# hub.net
KiCad netlist of a schematic drawn in EAGLE
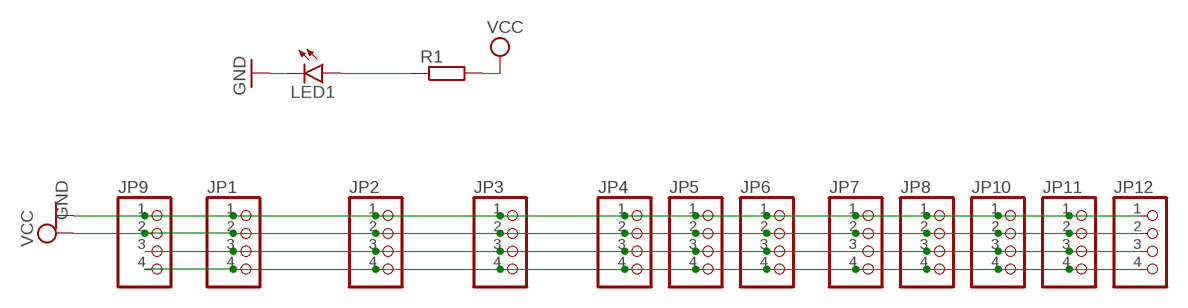
[diagram p0: schematic, sheet 1]

(export (version "E")
  (design (tool "Eeschema 10.0.6"))
  (components
    (comp (ref "JP1")
      (value "PINHD-1X04_2.54-SMD")
      (footprint "eagle-import:1X04SMD")
      (libsource (lib "eagle-import") (part "PINHD-1X04_2.54-SMD"))
    )
    (comp (ref "JP2")
      (value "PINHD-1X04_2.54-SMD")
      (footprint "eagle-import:1X04SMD")
      (libsource (lib "eagle-import") (part "PINHD-1X04_2.54-SMD"))
    )
    (comp (ref "JP3")
      (value "PINHD-1X04_2.54-SMD")
      (footprint "eagle-import:1X04SMD")
      (libsource (lib "eagle-import") (part "PINHD-1X04_2.54-SMD"))
    )
    (comp (ref "JP4")
      (value "PINHD-1X04_2.54-SMD")
      (footprint "eagle-import:1X04SMD")
      (libsource (lib "eagle-import") (part "PINHD-1X04_2.54-SMD"))
    )
    (comp (ref "JP5")
      (value "PINHD-1X04_2.54-SMD")
      (footprint "eagle-import:1X04SMD")
      (libsource (lib "eagle-import") (part "PINHD-1X04_2.54-SMD"))
    )
    (comp (ref "JP6")
      (value "PINHD-1X04_2.54-SMD")
      (footprint "eagle-import:1X04SMD")
      (libsource (lib "eagle-import") (part "PINHD-1X04_2.54-SMD"))
    )
    (comp (ref "JP7")
      (value "PINHD-1X04_2.54-SMD")
      (footprint "eagle-import:1X04SMD")
      (libsource (lib "eagle-import") (part "PINHD-1X04_2.54-SMD"))
    )
    (comp (ref "JP8")
      (value "PINHD-1X04_2.54-SMD")
      (footprint "eagle-import:1X04SMD")
      (libsource (lib "eagle-import") (part "PINHD-1X04_2.54-SMD"))
    )
    (comp (ref "JP9")
      (value "PINHD-1X04_2.54-SMD")
      (footprint "eagle-import:1X04SMD")
      (libsource (lib "eagle-import") (part "PINHD-1X04_2.54-SMD"))
    )
    (comp (ref "JP10")
      (value "PINHD-1X04_2.54-SMD")
      (footprint "eagle-import:1X04SMD")
      (libsource (lib "eagle-import") (part "PINHD-1X04_2.54-SMD"))
    )
    (comp (ref "JP11")
      (value "PINHD-1X04_2.54-SMD")
      (footprint "eagle-import:1X04SMD")
      (libsource (lib "eagle-import") (part "PINHD-1X04_2.54-SMD"))
    )
    (comp (ref "JP12")
      (value "PINHD-1X04_2.54-SMD")
      (footprint "eagle-import:1X04SMD")
      (libsource (lib "eagle-import") (part "PINHD-1X04_2.54-SMD"))
    )
    (comp (ref "LED1")
      (value "LEDCHIPLED_1206")
      (footprint "eagle-import:CHIPLED_1206")
      (libsource (lib "eagle-import") (part "LEDCHIPLED_1206"))
    )
    (comp (ref "R1")
      (value "R-EU_R1206")
      (footprint "eagle-import:R1206")
      (libsource (lib "eagle-import") (part "R-EU_R1206"))
    )
  )
  (nets
    (net (code "1") (name "GND") (class "Default")
      (node (ref "JP1") (pin "1") (pinfunction "1_1") (pintype "passive"))
      (node (ref "JP10") (pin "1") (pinfunction "1_1") (pintype "passive"))
      (node (ref "JP11") (pin "1") (pinfunction "1_1") (pintype "passive"))
      (node (ref "JP12") (pin "1") (pinfunction "1_1") (pintype "passive"))
      (node (ref "JP2") (pin "1") (pinfunction "1_1") (pintype "passive"))
      (node (ref "JP3") (pin "1") (pinfunction "1_1") (pintype "passive"))
      (node (ref "JP4") (pin "1") (pinfunction "1_1") (pintype "passive"))
      (node (ref "JP5") (pin "1") (pinfunction "1_1") (pintype "passive"))
      (node (ref "JP6") (pin "1") (pinfunction "1_1") (pintype "passive"))
      (node (ref "JP7") (pin "1") (pinfunction "1_1") (pintype "passive"))
      (node (ref "JP8") (pin "1") (pinfunction "1_1") (pintype "passive"))
      (node (ref "JP9") (pin "1") (pinfunction "1_1") (pintype "passive"))
      (node (ref "LED1") (pin "C") (pinfunction "C_C") (pintype "passive"))
    )
    (net (code "2") (name "Net-(JP1-Pad3)") (class "Default")
      (node (ref "JP1") (pin "3") (pinfunction "3_3") (pintype "passive"))
      (node (ref "JP10") (pin "3") (pinfunction "3_3") (pintype "passive"))
      (node (ref "JP11") (pin "3") (pinfunction "3_3") (pintype "passive"))
      (node (ref "JP12") (pin "3") (pinfunction "3_3") (pintype "passive"))
      (node (ref "JP2") (pin "3") (pinfunction "3_3") (pintype "passive"))
      (node (ref "JP3") (pin "3") (pinfunction "3_3") (pintype "passive"))
      (node (ref "JP4") (pin "3") (pinfunction "3_3") (pintype "passive"))
      (node (ref "JP5") (pin "3") (pinfunction "3_3") (pintype "passive"))
      (node (ref "JP6") (pin "3") (pinfunction "3_3") (pintype "passive"))
      (node (ref "JP7") (pin "3") (pinfunction "3_3") (pintype "passive"))
      (node (ref "JP8") (pin "3") (pinfunction "3_3") (pintype "passive"))
      (node (ref "JP9") (pin "3") (pinfunction "3_3") (pintype "passive"))
    )
    (net (code "3") (name "Net-(JP1-Pad4)") (class "Default")
      (node (ref "JP1") (pin "4") (pinfunction "4_4") (pintype "passive"))
      (node (ref "JP10") (pin "4") (pinfunction "4_4") (pintype "passive"))
      (node (ref "JP11") (pin "4") (pinfunction "4_4") (pintype "passive"))
      (node (ref "JP12") (pin "4") (pinfunction "4_4") (pintype "passive"))
      (node (ref "JP2") (pin "4") (pinfunction "4_4") (pintype "passive"))
      (node (ref "JP3") (pin "4") (pinfunction "4_4") (pintype "passive"))
      (node (ref "JP4") (pin "4") (pinfunction "4_4") (pintype "passive"))
      (node (ref "JP5") (pin "4") (pinfunction "4_4") (pintype "passive"))
      (node (ref "JP6") (pin "4") (pinfunction "4_4") (pintype "passive"))
      (node (ref "JP7") (pin "4") (pinfunction "4_4") (pintype "passive"))
      (node (ref "JP8") (pin "4") (pinfunction "4_4") (pintype "passive"))
      (node (ref "JP9") (pin "4") (pinfunction "4_4") (pintype "passive"))
    )
    (net (code "4") (name "Net-(LED1-PadA)") (class "Default")
      (node (ref "LED1") (pin "A") (pinfunction "A_A") (pintype "passive"))
      (node (ref "R1") (pin "1") (pinfunction "1_1") (pintype "passive"))
    )
    (net (code "5") (name "VCC") (class "Default")
      (node (ref "JP1") (pin "2") (pinfunction "2_2") (pintype "passive"))
      (node (ref "JP10") (pin "2") (pinfunction "2_2") (pintype "passive"))
      (node (ref "JP11") (pin "2") (pinfunction "2_2") (pintype "passive"))
      (node (ref "JP12") (pin "2") (pinfunction "2_2") (pintype "passive"))
      (node (ref "JP2") (pin "2") (pinfunction "2_2") (pintype "passive"))
      (node (ref "JP3") (pin "2") (pinfunction "2_2") (pintype "passive"))
      (node (ref "JP4") (pin "2") (pinfunction "2_2") (pintype "passive"))
      (node (ref "JP5") (pin "2") (pinfunction "2_2") (pintype "passive"))
      (node (ref "JP6") (pin "2") (pinfunction "2_2") (pintype "passive"))
      (node (ref "JP7") (pin "2") (pinfunction "2_2") (pintype "passive"))
      (node (ref "JP8") (pin "2") (pinfunction "2_2") (pintype "passive"))
      (node (ref "JP9") (pin "2") (pinfunction "2_2") (pintype "passive"))
      (node (ref "R1") (pin "2") (pinfunction "2_2") (pintype "passive"))
    )
  )
)
